# spine_0.net
KiCad netlist of a schematic drawn in Altium Designer
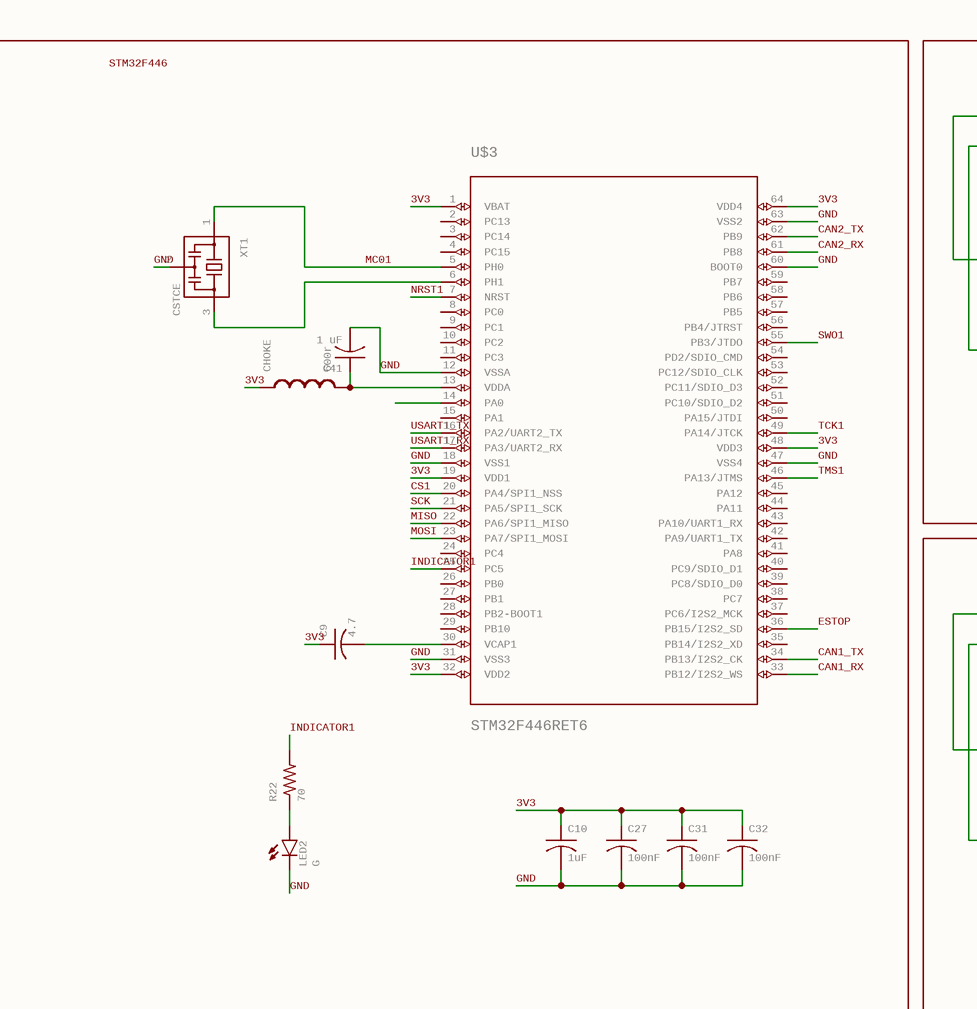
[diagram p0: spine_0.SchDoc, top left]
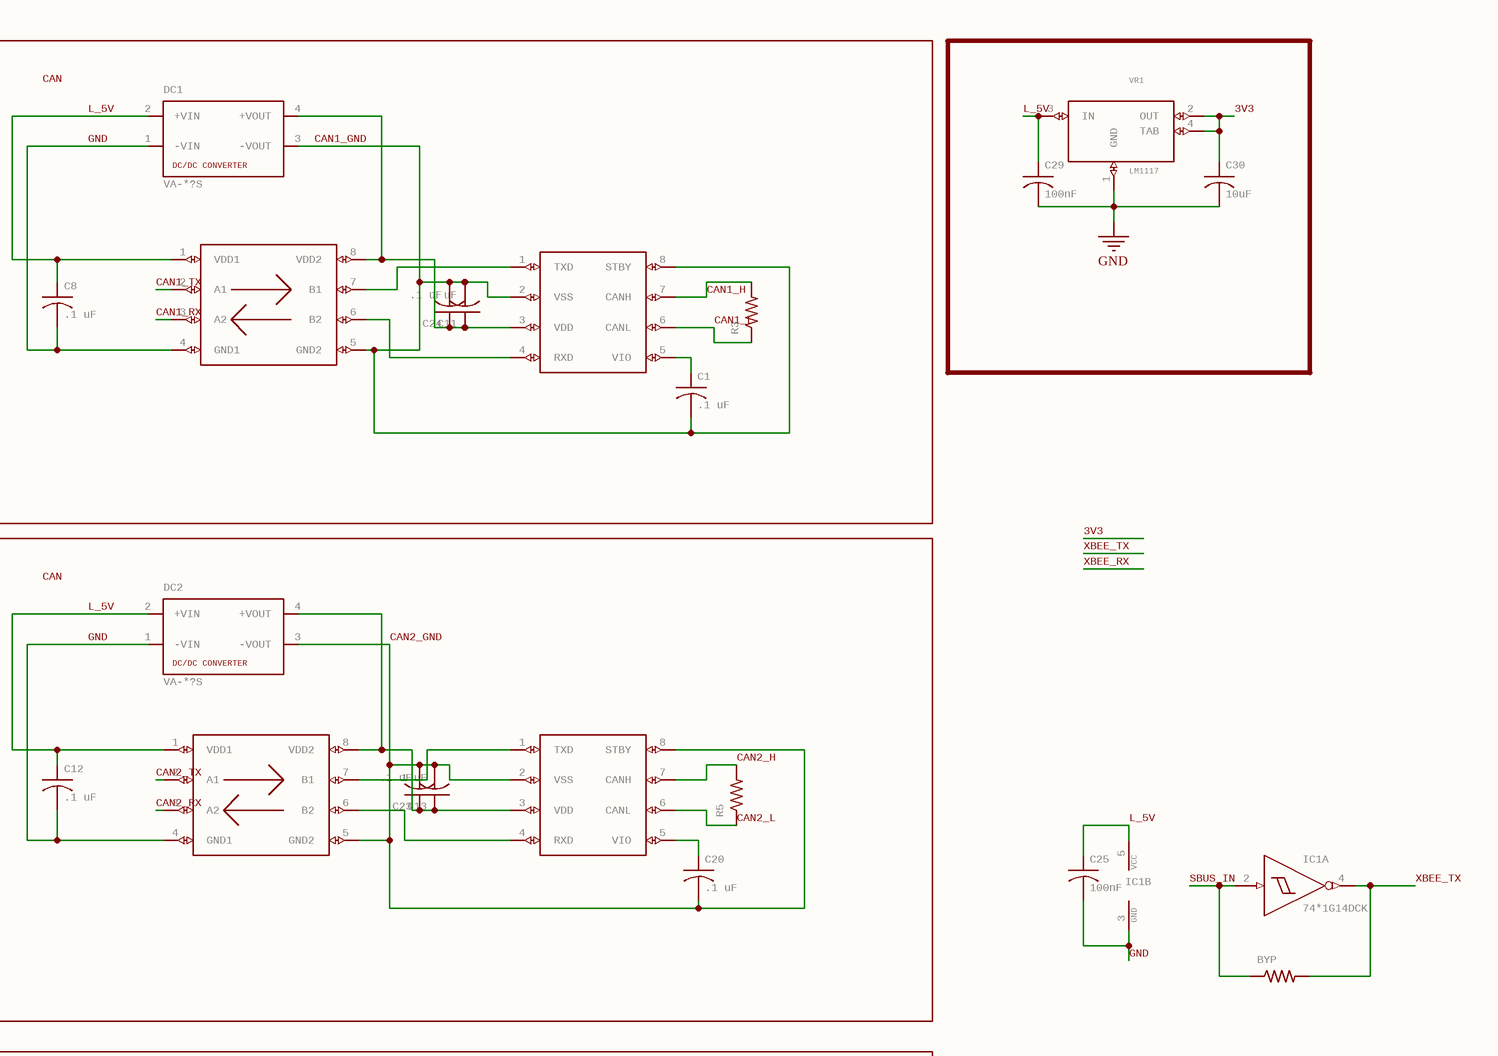
[diagram p1: spine_0.SchDoc, top right]
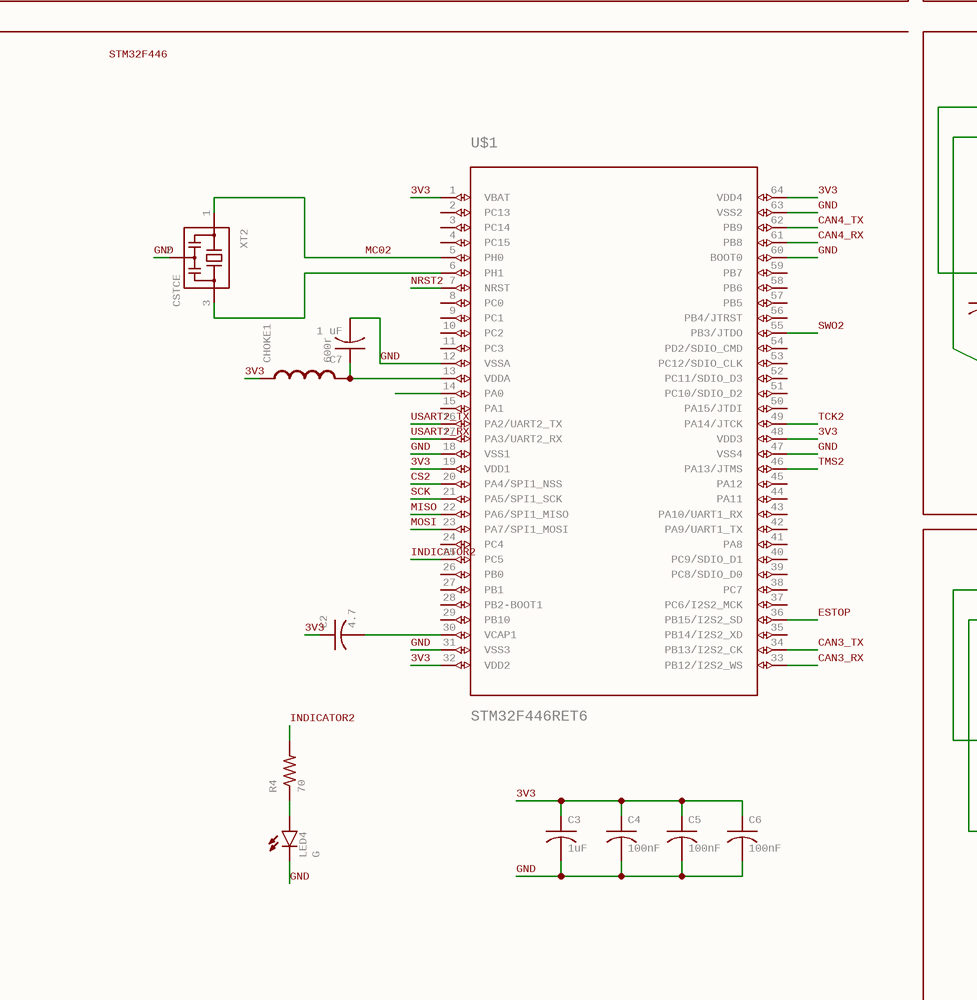
[diagram p2: spine_0.SchDoc, bottom left]
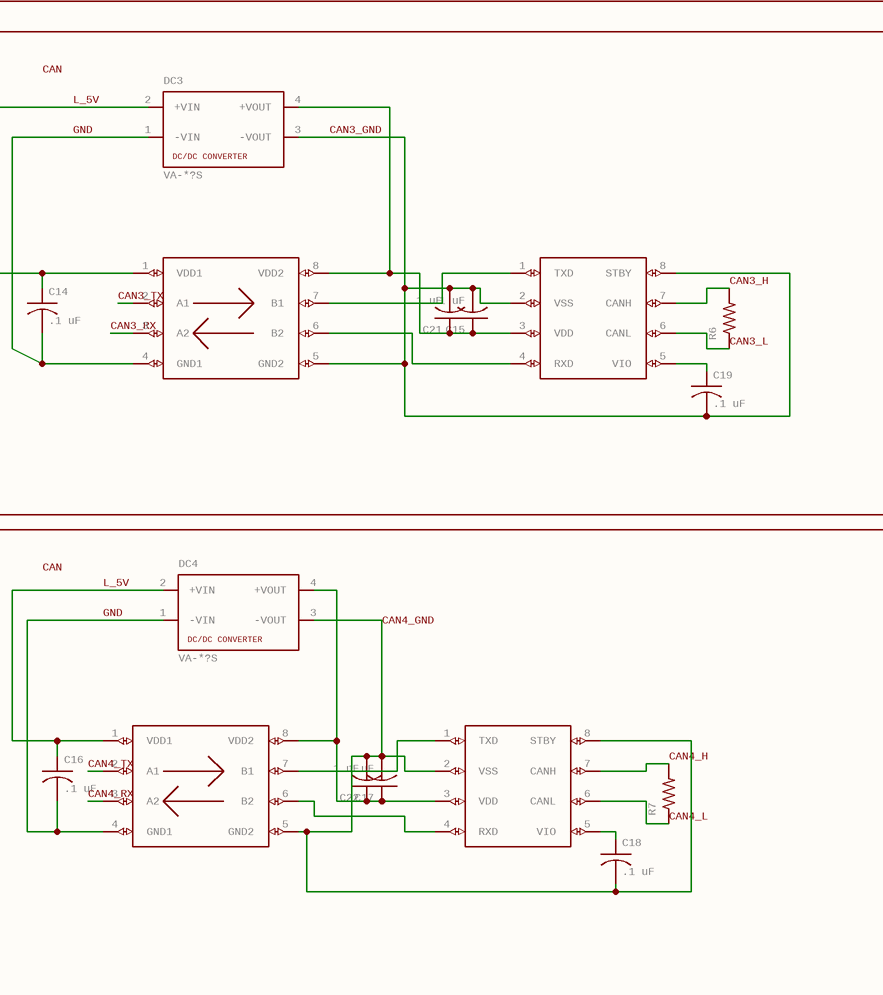
[diagram p3: spine_0.SchDoc, bottom right]

(export (version "E")
  (design (tool "Eeschema 10.0.6"))
  (components
    (comp (ref "BYP")
      (value "R-US_R0402")
      (footprint "R0402")
      (description "RESISTOR, American symbol")
      (libsource (lib "rcl") (part "R-US_R0402"))
    )
    (comp (ref "C1")
      (value ".1 uF")
      (footprint "C0603K")
      (description "CAPACITOR, American symbol")
      (libsource (lib "rcl") (part "C-USC0603K"))
    )
    (comp (ref "C2")
      (value "4.7")
      (footprint "C0603")
      (description "CAPACITOR, American symbol")
      (libsource (lib "rcl") (part "C-USC0603"))
    )
    (comp (ref "C3")
      (value "1uF")
      (footprint "C0603")
      (description "CAPACITOR, American symbol")
      (libsource (lib "rcl") (part "C-USC0603"))
    )
    (comp (ref "C4")
      (value "100nF")
      (footprint "C0603")
      (description "CAPACITOR, American symbol")
      (libsource (lib "rcl") (part "C-USC0603"))
    )
    (comp (ref "C5")
      (value "100nF")
      (footprint "C0603")
      (description "CAPACITOR, American symbol")
      (libsource (lib "rcl") (part "C-USC0603"))
    )
    (comp (ref "C6")
      (value "100nF")
      (footprint "C0603")
      (description "CAPACITOR, American symbol")
      (libsource (lib "rcl") (part "C-USC0603"))
    )
    (comp (ref "C7")
      (value "1 uF")
      (footprint "C0603")
      (description "CAPACITOR, American symbol")
      (libsource (lib "rcl") (part "C-USC0603"))
    )
    (comp (ref "C8")
      (value ".1 uF")
      (footprint "C0603K")
      (description "CAPACITOR, American symbol")
      (libsource (lib "rcl") (part "C-USC0603K"))
    )
    (comp (ref "C9")
      (value "4.7")
      (footprint "C0603")
      (description "CAPACITOR, American symbol")
      (libsource (lib "rcl") (part "C-USC0603"))
    )
    (comp (ref "C10")
      (value "1uF")
      (footprint "C0603")
      (description "CAPACITOR, American symbol")
      (libsource (lib "rcl") (part "C-USC0603"))
    )
    (comp (ref "C11")
      (value "1 uF")
      (footprint "C0603K")
      (description "CAPACITOR, American symbol")
      (libsource (lib "rcl") (part "C-USC0603K"))
    )
    (comp (ref "C12")
      (value ".1 uF")
      (footprint "C0603K")
      (description "CAPACITOR, American symbol")
      (libsource (lib "rcl") (part "C-USC0603K"))
    )
    (comp (ref "C13")
      (value "1 uF")
      (footprint "C0603K")
      (description "CAPACITOR, American symbol")
      (libsource (lib "rcl") (part "C-USC0603K"))
    )
    (comp (ref "C14")
      (value ".1 uF")
      (footprint "C0603K")
      (description "CAPACITOR, American symbol")
      (libsource (lib "rcl") (part "C-USC0603K"))
    )
    (comp (ref "C15")
      (value "1 uF")
      (footprint "C0603K")
      (description "CAPACITOR, American symbol")
      (libsource (lib "rcl") (part "C-USC0603K"))
    )
    (comp (ref "C16")
      (value ".1 uF")
      (footprint "C0603K")
      (description "CAPACITOR, American symbol")
      (libsource (lib "rcl") (part "C-USC0603K"))
    )
    (comp (ref "C17")
      (value "1 uF")
      (footprint "C0603K")
      (description "CAPACITOR, American symbol")
      (libsource (lib "rcl") (part "C-USC0603K"))
    )
    (comp (ref "C18")
      (value ".1 uF")
      (footprint "C0603K")
      (description "CAPACITOR, American symbol")
      (libsource (lib "rcl") (part "C-USC0603K"))
    )
    (comp (ref "C19")
      (value ".1 uF")
      (footprint "C0603K")
      (description "CAPACITOR, American symbol")
      (libsource (lib "rcl") (part "C-USC0603K"))
    )
    (comp (ref "C20")
      (value ".1 uF")
      (footprint "C0603K")
      (description "CAPACITOR, American symbol")
      (libsource (lib "rcl") (part "C-USC0603K"))
    )
    (comp (ref "C21")
      (value ".1 uF")
      (footprint "C0603K")
      (description "CAPACITOR, American symbol")
      (libsource (lib "rcl") (part "C-USC0603K"))
    )
    (comp (ref "C22")
      (value ".1 uF")
      (footprint "C0603K")
      (description "CAPACITOR, American symbol")
      (libsource (lib "rcl") (part "C-USC0603K"))
    )
    (comp (ref "C23")
      (value ".1 uF")
      (footprint "C0603K")
      (description "CAPACITOR, American symbol")
      (libsource (lib "rcl") (part "C-USC0603K"))
    )
    (comp (ref "C24")
      (value ".1 uF")
      (footprint "C0603K")
      (description "CAPACITOR, American symbol")
      (libsource (lib "rcl") (part "C-USC0603K"))
    )
    (comp (ref "C25")
      (value "100nF")
      (footprint "C0603")
      (description "CAPACITOR, American symbol")
      (libsource (lib "rcl") (part "C-USC0603"))
    )
    (comp (ref "C27")
      (value "100nF")
      (footprint "C0603")
      (description "CAPACITOR, American symbol")
      (libsource (lib "rcl") (part "C-USC0603"))
    )
    (comp (ref "C29")
      (value "100nF")
      (footprint "C0603")
      (description "CAPACITOR, American symbol")
      (libsource (lib "rcl") (part "C-USC0603"))
    )
    (comp (ref "C30")
      (value "10uF")
      (footprint "C0805K")
      (description "CAPACITOR, American symbol")
      (libsource (lib "rcl") (part "C-USC0805K"))
    )
    (comp (ref "C31")
      (value "100nF")
      (footprint "C0603")
      (description "CAPACITOR, American symbol")
      (libsource (lib "rcl") (part "C-USC0603"))
    )
    (comp (ref "C32")
      (value "100nF")
      (footprint "C0603")
      (description "CAPACITOR, American symbol")
      (libsource (lib "rcl") (part "C-USC0603"))
    )
    (comp (ref "C41")
      (value "1 uF")
      (footprint "C0603")
      (description "CAPACITOR, American symbol")
      (libsource (lib "rcl") (part "C-USC0603"))
    )
    (comp (ref "CHOKE")
      (value "600r")
      (footprint "0603")
      (libsource (lib "SparkFun-Passives") (part "INDUCTOR0603"))
    )
    (comp (ref "CHOKE1")
      (value "600r")
      (footprint "0603")
      (libsource (lib "SparkFun-Passives") (part "INDUCTOR0603"))
    )
    (comp (ref "DC1")
      (value "VA-*?S")
      (footprint "4SIL")
      (description "DC DC Converter Single Output, 1 Watt   Motien Technology Co.,Ltd. Source:  Data sheet")
      (fields
        (field (name "DC/DCCONVERTER") "DC/DC CONVERTER")
        (field (name "MF") "MF")
        (field (name "MPN") "MPN")
      )
      (libsource (lib "dc-dc-converter") (part "VA-*?S"))
    )
    (comp (ref "DC2")
      (value "VA-*?S")
      (footprint "4SIL")
      (description "DC DC Converter Single Output, 1 Watt   Motien Technology Co.,Ltd. Source:  Data sheet")
      (fields
        (field (name "DC/DCCONVERTER") "DC/DC CONVERTER")
        (field (name "MF") "MF")
        (field (name "MPN") "MPN")
      )
      (libsource (lib "dc-dc-converter") (part "VA-*?S"))
    )
    (comp (ref "DC3")
      (value "VA-*?S")
      (footprint "4SIL")
      (description "DC DC Converter Single Output, 1 Watt   Motien Technology Co.,Ltd. Source:  Data sheet")
      (fields
        (field (name "DC/DCCONVERTER") "DC/DC CONVERTER")
        (field (name "MF") "MF")
        (field (name "MPN") "MPN")
      )
      (libsource (lib "dc-dc-converter") (part "VA-*?S"))
    )
    (comp (ref "DC4")
      (value "VA-*?S")
      (footprint "4SIL")
      (description "DC DC Converter Single Output, 1 Watt   Motien Technology Co.,Ltd. Source:  Data sheet")
      (fields
        (field (name "DC/DCCONVERTER") "DC/DC CONVERTER")
        (field (name "MF") "MF")
        (field (name "MPN") "MPN")
      )
      (libsource (lib "dc-dc-converter") (part "VA-*?S"))
    )
    (comp (ref "IC1")
      (value "74*1G14DCK")
      (footprint "SC70-5")
      (description "Single Schmitt-Trigger Inverter Gate")
      (fields (field (name "GND") "GND") (field (name "VCC") "VCC"))
      (libsource (lib "74xx-little-us") (part "74*1G14DCK"))
    )
    (comp (ref "LED2") (value "G") (footprint "LED-0603") (libsource (lib "SparkFun-LED") (part "LED0603")))
    (comp (ref "LED4") (value "G") (footprint "LED-0603") (libsource (lib "SparkFun-LED") (part "LED0603")))
    (comp (ref "R3")
      (value "R-US_R0402")
      (footprint "R0402")
      (description "RESISTOR, American symbol")
      (libsource (lib "rcl") (part "R-US_R0402"))
    )
    (comp (ref "R4")
      (value "70")
      (footprint "R0603")
      (description "RESISTOR, American symbol")
      (libsource (lib "rcl") (part "R-US_R0603"))
    )
    (comp (ref "R5")
      (value "R-US_R0402")
      (footprint "R0402")
      (description "RESISTOR, American symbol")
      (libsource (lib "rcl") (part "R-US_R0402"))
    )
    (comp (ref "R6")
      (value "R-US_R0402")
      (footprint "R0402")
      (description "RESISTOR, American symbol")
      (libsource (lib "rcl") (part "R-US_R0402"))
    )
    (comp (ref "R7")
      (value "R-US_R0402")
      (footprint "R0402")
      (description "RESISTOR, American symbol")
      (libsource (lib "rcl") (part "R-US_R0402"))
    )
    (comp (ref "R22")
      (value "70")
      (footprint "R0603")
      (description "RESISTOR, American symbol")
      (libsource (lib "rcl") (part "R-US_R0603"))
    )
    (comp (ref "U$1")
      (value "STM32F446RET6")
      (footprint "TQFP64")
      (description "ARM DSP Chip used on the WAV Trigger board.")
      (fields (field (name "LIBRARYNAME") "BenLibrary"))
      (libsource (lib "BenLibrary") (part "STM32F446RET6"))
    )
    (comp (ref "U$3")
      (value "STM32F446RET6")
      (footprint "TQFP64")
      (description "ARM DSP Chip used on the WAV Trigger board.")
      (fields (field (name "LIBRARYNAME") "BenLibrary"))
      (libsource (lib "BenLibrary") (part "STM32F446RET6"))
    )
    (comp (ref "U$4")
      (value "MCP2561")
      (footprint "SO08")
      (fields (field (name "LIBRARYNAME") "BenLibrary"))
      (libsource (lib "BenLibrary") (part "MCP2561"))
    )
    (comp (ref "U$5")
      (value "MCP2561")
      (footprint "SO08")
      (fields (field (name "LIBRARYNAME") "BenLibrary"))
      (libsource (lib "BenLibrary") (part "MCP2561"))
    )
    (comp (ref "U$6")
      (value "MCP2561")
      (footprint "SO08")
      (fields (field (name "LIBRARYNAME") "BenLibrary"))
      (libsource (lib "BenLibrary") (part "MCP2561"))
    )
    (comp (ref "U$7")
      (value "MCP2561")
      (footprint "SO08")
      (fields (field (name "LIBRARYNAME") "BenLibrary"))
      (libsource (lib "BenLibrary") (part "MCP2561"))
    )
    (comp (ref "U$8")
      (value "SI8410")
      (footprint "SO08")
      (fields (field (name "LIBRARYNAME") "BenLibrary"))
      (libsource (lib "BenLibrary") (part "SI8410"))
    )
    (comp (ref "U$9")
      (value "SI8410")
      (footprint "SO08")
      (fields (field (name "LIBRARYNAME") "BenLibrary"))
      (libsource (lib "BenLibrary") (part "SI8410"))
    )
    (comp (ref "U$10")
      (value "SI8410")
      (footprint "SO08")
      (fields (field (name "LIBRARYNAME") "BenLibrary"))
      (libsource (lib "BenLibrary") (part "SI8410"))
    )
    (comp (ref "U$11")
      (value "SI8410")
      (footprint "SO08")
      (fields (field (name "LIBRARYNAME") "BenLibrary"))
      (libsource (lib "BenLibrary") (part "SI8410"))
    )
    (comp (ref "VR1")
      (value "LM1117")
      (footprint "SOT-223")
      (fields (field (name "LIBRARYNAME") "sc_usercreated"))
      (libsource (lib "sc_usercreated") (part "LM1117"))
    )
    (comp (ref "XT1")
      (value "CSTCE")
      (footprint "CSTCE")
      (fields (field (name "LIBRARYNAME") "sc_usercreated"))
      (libsource (lib "sc_usercreated") (part "CSTCE"))
    )
    (comp (ref "XT2")
      (value "CSTCE")
      (footprint "CSTCE")
      (fields (field (name "LIBRARYNAME") "sc_usercreated"))
      (libsource (lib "sc_usercreated") (part "CSTCE"))
    )
  )
  (nets
    (net (code "1") (name "/3V3") (class "Default")
      (node (ref "C10") (pin "1") (pinfunction "1_1") (pintype "passive"))
      (node (ref "C2") (pin "1") (pinfunction "1_1") (pintype "passive"))
      (node (ref "C27") (pin "1") (pinfunction "1_1") (pintype "passive"))
      (node (ref "C3") (pin "1") (pinfunction "1_1") (pintype "passive"))
      (node (ref "C30") (pin "1") (pinfunction "1_1") (pintype "passive"))
      (node (ref "C31") (pin "1") (pinfunction "1_1") (pintype "passive"))
      (node (ref "C32") (pin "1") (pinfunction "1_1") (pintype "passive"))
      (node (ref "C4") (pin "1") (pinfunction "1_1") (pintype "passive"))
      (node (ref "C5") (pin "1") (pinfunction "1_1") (pintype "passive"))
      (node (ref "C6") (pin "1") (pinfunction "1_1") (pintype "passive"))
      (node (ref "C9") (pin "1") (pinfunction "1_1") (pintype "passive"))
      (node (ref "CHOKE") (pin "1") (pinfunction "1_1") (pintype "passive"))
      (node (ref "CHOKE1") (pin "1") (pinfunction "1_1") (pintype "passive"))
      (node (ref "U$1") (pin "1") (pinfunction "VBAT_1") (pintype "bidirectional"))
      (node (ref "U$1") (pin "19") (pinfunction "VDD1_19") (pintype "bidirectional"))
      (node (ref "U$1") (pin "32") (pinfunction "VDD2_32") (pintype "bidirectional"))
      (node (ref "U$1") (pin "48") (pinfunction "VDD3_48") (pintype "bidirectional"))
      (node (ref "U$1") (pin "64") (pinfunction "VDD4_64") (pintype "bidirectional"))
      (node (ref "U$3") (pin "1") (pinfunction "VBAT_1") (pintype "bidirectional"))
      (node (ref "U$3") (pin "19") (pinfunction "VDD1_19") (pintype "bidirectional"))
      (node (ref "U$3") (pin "32") (pinfunction "VDD2_32") (pintype "bidirectional"))
      (node (ref "U$3") (pin "48") (pinfunction "VDD3_48") (pintype "bidirectional"))
      (node (ref "U$3") (pin "64") (pinfunction "VDD4_64") (pintype "bidirectional"))
      (node (ref "VR1") (pin "2") (pinfunction "OUT_2") (pintype "bidirectional"))
      (node (ref "VR1") (pin "4") (pinfunction "TAB_4") (pintype "bidirectional"))
    )
    (net (code "2") (name "/CAN1_GND") (class "Default")
      (node (ref "C1") (pin "2") (pinfunction "2_2") (pintype "passive"))
      (node (ref "C11") (pin "2") (pinfunction "2_2") (pintype "passive"))
      (node (ref "C24") (pin "2") (pinfunction "2_2") (pintype "passive"))
      (node (ref "DC1") (pin "3") (pinfunction "-VOUT_3") (pintype "passive"))
      (node (ref "U$4") (pin "2") (pinfunction "VSS_2") (pintype "bidirectional"))
      (node (ref "U$4") (pin "8") (pinfunction "STBY_8") (pintype "bidirectional"))
      (node (ref "U$8") (pin "5") (pinfunction "GND2_5") (pintype "bidirectional"))
    )
    (net (code "3") (name "/CAN1_H") (class "Default")
      (node (ref "R3") (pin "2") (pinfunction "2_2") (pintype "passive"))
      (node (ref "U$4") (pin "7") (pinfunction "CANH_7") (pintype "bidirectional"))
    )
    (net (code "4") (name "/CAN1_L") (class "Default")
      (node (ref "R3") (pin "1") (pinfunction "1_1") (pintype "passive"))
      (node (ref "U$4") (pin "6") (pinfunction "CANL_6") (pintype "bidirectional"))
    )
    (net (code "5") (name "/CAN1_RX") (class "Default")
      (node (ref "U$3") (pin "33") (pinfunction "PB12/I2S2_WS_33") (pintype "bidirectional"))
      (node (ref "U$8") (pin "3") (pinfunction "A2_3") (pintype "bidirectional"))
    )
    (net (code "6") (name "/CAN1_TX") (class "Default")
      (node (ref "U$3") (pin "34") (pinfunction "PB13/I2S2_CK_34") (pintype "bidirectional"))
      (node (ref "U$8") (pin "2") (pinfunction "A1_2") (pintype "bidirectional"))
    )
    (net (code "7") (name "/CAN2_GND") (class "Default")
      (node (ref "C13") (pin "2") (pinfunction "2_2") (pintype "passive"))
      (node (ref "C20") (pin "2") (pinfunction "2_2") (pintype "passive"))
      (node (ref "C23") (pin "2") (pinfunction "2_2") (pintype "passive"))
      (node (ref "DC2") (pin "3") (pinfunction "-VOUT_3") (pintype "passive"))
      (node (ref "U$10") (pin "5") (pinfunction "GND2_5") (pintype "bidirectional"))
      (node (ref "U$5") (pin "2") (pinfunction "VSS_2") (pintype "bidirectional"))
      (node (ref "U$5") (pin "8") (pinfunction "STBY_8") (pintype "bidirectional"))
    )
    (net (code "8") (name "/CAN2_H") (class "Default")
      (node (ref "R5") (pin "2") (pinfunction "2_2") (pintype "passive"))
      (node (ref "U$5") (pin "7") (pinfunction "CANH_7") (pintype "bidirectional"))
    )
    (net (code "9") (name "/CAN2_L") (class "Default")
      (node (ref "R5") (pin "1") (pinfunction "1_1") (pintype "passive"))
      (node (ref "U$5") (pin "6") (pinfunction "CANL_6") (pintype "bidirectional"))
    )
    (net (code "10") (name "/CAN2_RX") (class "Default")
      (node (ref "U$10") (pin "3") (pinfunction "A2_3") (pintype "bidirectional"))
      (node (ref "U$3") (pin "61") (pinfunction "PB8_61") (pintype "bidirectional"))
    )
    (net (code "11") (name "/CAN2_TX") (class "Default")
      (node (ref "U$10") (pin "2") (pinfunction "A1_2") (pintype "bidirectional"))
      (node (ref "U$3") (pin "62") (pinfunction "PB9_62") (pintype "bidirectional"))
    )
    (net (code "12") (name "/CAN3_GND") (class "Default")
      (node (ref "C15") (pin "2") (pinfunction "2_2") (pintype "passive"))
      (node (ref "C19") (pin "2") (pinfunction "2_2") (pintype "passive"))
      (node (ref "C21") (pin "2") (pinfunction "2_2") (pintype "passive"))
      (node (ref "DC3") (pin "3") (pinfunction "-VOUT_3") (pintype "passive"))
      (node (ref "U$6") (pin "2") (pinfunction "VSS_2") (pintype "bidirectional"))
      (node (ref "U$6") (pin "8") (pinfunction "STBY_8") (pintype "bidirectional"))
      (node (ref "U$9") (pin "5") (pinfunction "GND2_5") (pintype "bidirectional"))
    )
    (net (code "13") (name "/CAN3_H") (class "Default")
      (node (ref "R6") (pin "2") (pinfunction "2_2") (pintype "passive"))
      (node (ref "U$6") (pin "7") (pinfunction "CANH_7") (pintype "bidirectional"))
    )
    (net (code "14") (name "/CAN3_L") (class "Default")
      (node (ref "R6") (pin "1") (pinfunction "1_1") (pintype "passive"))
      (node (ref "U$6") (pin "6") (pinfunction "CANL_6") (pintype "bidirectional"))
    )
    (net (code "15") (name "/CAN3_RX") (class "Default")
      (node (ref "U$1") (pin "33") (pinfunction "PB12/I2S2_WS_33") (pintype "bidirectional"))
      (node (ref "U$9") (pin "3") (pinfunction "A2_3") (pintype "bidirectional"))
    )
    (net (code "16") (name "/CAN3_TX") (class "Default")
      (node (ref "U$1") (pin "34") (pinfunction "PB13/I2S2_CK_34") (pintype "bidirectional"))
      (node (ref "U$9") (pin "2") (pinfunction "A1_2") (pintype "bidirectional"))
    )
    (net (code "17") (name "/CAN4_GND") (class "Default")
      (node (ref "C17") (pin "2") (pinfunction "2_2") (pintype "passive"))
      (node (ref "C18") (pin "2") (pinfunction "2_2") (pintype "passive"))
      (node (ref "C22") (pin "2") (pinfunction "2_2") (pintype "passive"))
      (node (ref "DC4") (pin "3") (pinfunction "-VOUT_3") (pintype "passive"))
      (node (ref "U$11") (pin "5") (pinfunction "GND2_5") (pintype "bidirectional"))
      (node (ref "U$7") (pin "2") (pinfunction "VSS_2") (pintype "bidirectional"))
      (node (ref "U$7") (pin "8") (pinfunction "STBY_8") (pintype "bidirectional"))
    )
    (net (code "18") (name "/CAN4_H") (class "Default")
      (node (ref "R7") (pin "2") (pinfunction "2_2") (pintype "passive"))
      (node (ref "U$7") (pin "7") (pinfunction "CANH_7") (pintype "bidirectional"))
    )
    (net (code "19") (name "/CAN4_L") (class "Default")
      (node (ref "R7") (pin "1") (pinfunction "1_1") (pintype "passive"))
      (node (ref "U$7") (pin "6") (pinfunction "CANL_6") (pintype "bidirectional"))
    )
    (net (code "20") (name "/CAN4_RX") (class "Default")
      (node (ref "U$1") (pin "61") (pinfunction "PB8_61") (pintype "bidirectional"))
      (node (ref "U$11") (pin "3") (pinfunction "A2_3") (pintype "bidirectional"))
    )
    (net (code "21") (name "/CAN4_TX") (class "Default")
      (node (ref "U$1") (pin "62") (pinfunction "PB9_62") (pintype "bidirectional"))
      (node (ref "U$11") (pin "2") (pinfunction "A1_2") (pintype "bidirectional"))
    )
    (net (code "22") (name "/CS1") (class "Default")
      (node (ref "U$3") (pin "20") (pinfunction "PA4/SPI1_NSS_20") (pintype "bidirectional"))
    )
    (net (code "23") (name "/CS2") (class "Default")
      (node (ref "U$1") (pin "20") (pinfunction "PA4/SPI1_NSS_20") (pintype "bidirectional"))
    )
    (net (code "24") (name "/ESTOP") (class "Default")
      (node (ref "U$1") (pin "36") (pinfunction "PB15/I2S2_SD_36") (pintype "bidirectional"))
      (node (ref "U$3") (pin "36") (pinfunction "PB15/I2S2_SD_36") (pintype "bidirectional"))
    )
    (net (code "25") (name "/INDICATOR1") (class "Default")
      (node (ref "R22") (pin "2") (pinfunction "2_2") (pintype "passive"))
      (node (ref "U$3") (pin "25") (pinfunction "PC5_25") (pintype "bidirectional"))
    )
    (net (code "26") (name "/INDICATOR2") (class "Default")
      (node (ref "R4") (pin "2") (pinfunction "2_2") (pintype "passive"))
      (node (ref "U$1") (pin "25") (pinfunction "PC5_25") (pintype "bidirectional"))
    )
    (net (code "27") (name "/L_5V") (class "Default")
      (node (ref "C12") (pin "1") (pinfunction "1_1") (pintype "passive"))
      (node (ref "C14") (pin "1") (pinfunction "1_1") (pintype "passive"))
      (node (ref "C16") (pin "1") (pinfunction "1_1") (pintype "passive"))
      (node (ref "C25") (pin "1") (pinfunction "1_1") (pintype "passive"))
      (node (ref "C29") (pin "1") (pinfunction "1_1") (pintype "passive"))
      (node (ref "C8") (pin "1") (pinfunction "1_1") (pintype "passive"))
      (node (ref "DC1") (pin "2") (pinfunction "+VIN_2") (pintype "passive"))
      (node (ref "DC2") (pin "2") (pinfunction "+VIN_2") (pintype "passive"))
      (node (ref "DC3") (pin "2") (pinfunction "+VIN_2") (pintype "passive"))
      (node (ref "DC4") (pin "2") (pinfunction "+VIN_2") (pintype "passive"))
      (node (ref "IC1") (pin "5") (pinfunction "VCC_5") (pintype "power_in"))
      (node (ref "U$10") (pin "1") (pinfunction "VDD1_1") (pintype "bidirectional"))
      (node (ref "U$11") (pin "1") (pinfunction "VDD1_1") (pintype "bidirectional"))
      (node (ref "U$8") (pin "1") (pinfunction "VDD1_1") (pintype "bidirectional"))
      (node (ref "U$9") (pin "1") (pinfunction "VDD1_1") (pintype "bidirectional"))
      (node (ref "VR1") (pin "3") (pinfunction "IN_3") (pintype "bidirectional"))
    )
    (net (code "28") (name "/MC01") (class "Default")
      (node (ref "U$3") (pin "5") (pinfunction "PH0_5") (pintype "bidirectional"))
      (node (ref "XT1") (pin "1") (pinfunction "1_1") (pintype "passive"))
    )
    (net (code "29") (name "/MC02") (class "Default")
      (node (ref "U$1") (pin "5") (pinfunction "PH0_5") (pintype "bidirectional"))
      (node (ref "XT2") (pin "1") (pinfunction "1_1") (pintype "passive"))
    )
    (net (code "30") (name "/MISO") (class "Default")
      (node (ref "U$1") (pin "22") (pinfunction "PA6/SPI1_MISO_22") (pintype "bidirectional"))
      (node (ref "U$3") (pin "22") (pinfunction "PA6/SPI1_MISO_22") (pintype "bidirectional"))
    )
    (net (code "31") (name "/MOSI") (class "Default")
      (node (ref "U$1") (pin "23") (pinfunction "PA7/SPI1_MOSI_23") (pintype "bidirectional"))
      (node (ref "U$3") (pin "23") (pinfunction "PA7/SPI1_MOSI_23") (pintype "bidirectional"))
    )
    (net (code "32") (name "/NRST1") (class "Default")
      (node (ref "U$3") (pin "7") (pinfunction "NRST_7") (pintype "bidirectional"))
    )
    (net (code "33") (name "/NRST2") (class "Default")
      (node (ref "U$1") (pin "7") (pinfunction "NRST_7") (pintype "bidirectional"))
    )
    (net (code "34") (name "/SBUS_IN") (class "Default")
      (node (ref "BYP") (pin "1") (pinfunction "1_1") (pintype "passive"))
      (node (ref "IC1") (pin "2") (pinfunction "I_2") (pintype "input"))
    )
    (net (code "35") (name "/SCK") (class "Default")
      (node (ref "U$1") (pin "21") (pinfunction "PA5/SPI1_SCK_21") (pintype "bidirectional"))
      (node (ref "U$3") (pin "21") (pinfunction "PA5/SPI1_SCK_21") (pintype "bidirectional"))
    )
    (net (code "36") (name "/SWO1") (class "Default")
      (node (ref "U$3") (pin "55") (pinfunction "PB3/JTDO_55") (pintype "bidirectional"))
    )
    (net (code "37") (name "/SWO2") (class "Default")
      (node (ref "U$1") (pin "55") (pinfunction "PB3/JTDO_55") (pintype "bidirectional"))
    )
    (net (code "38") (name "/TCK1") (class "Default")
      (node (ref "U$3") (pin "49") (pinfunction "PA14/JTCK_49") (pintype "bidirectional"))
    )
    (net (code "39") (name "/TCK2") (class "Default")
      (node (ref "U$1") (pin "49") (pinfunction "PA14/JTCK_49") (pintype "bidirectional"))
    )
    (net (code "40") (name "/TMS1") (class "Default")
      (node (ref "U$3") (pin "46") (pinfunction "PA13/JTMS_46") (pintype "bidirectional"))
    )
    (net (code "41") (name "/TMS2") (class "Default")
      (node (ref "U$1") (pin "46") (pinfunction "PA13/JTMS_46") (pintype "bidirectional"))
    )
    (net (code "42") (name "/USART1_RX") (class "Default")
      (node (ref "U$3") (pin "17") (pinfunction "PA3/UART2_RX_17") (pintype "bidirectional"))
    )
    (net (code "43") (name "/USART1_TX") (class "Default")
      (node (ref "U$3") (pin "16") (pinfunction "PA2/UART2_TX_16") (pintype "bidirectional"))
    )
    (net (code "44") (name "/USART2_RX") (class "Default")
      (node (ref "U$1") (pin "17") (pinfunction "PA3/UART2_RX_17") (pintype "bidirectional"))
    )
    (net (code "45") (name "/USART2_TX") (class "Default")
      (node (ref "U$1") (pin "16") (pinfunction "PA2/UART2_TX_16") (pintype "bidirectional"))
    )
    (net (code "47") (name "/XBEE_TX") (class "Default")
      (node (ref "BYP") (pin "2") (pinfunction "2_2") (pintype "passive"))
      (node (ref "IC1") (pin "4") (pinfunction "O_4") (pintype "output"))
    )
    (net (code "48") (name "GND") (class "Default")
      (node (ref "C10") (pin "2") (pinfunction "2_2") (pintype "passive"))
      (node (ref "C12") (pin "2") (pinfunction "2_2") (pintype "passive"))
      (node (ref "C14") (pin "2") (pinfunction "2_2") (pintype "passive"))
      (node (ref "C16") (pin "2") (pinfunction "2_2") (pintype "passive"))
      (node (ref "C25") (pin "2") (pinfunction "2_2") (pintype "passive"))
      (node (ref "C27") (pin "2") (pinfunction "2_2") (pintype "passive"))
      (node (ref "C29") (pin "2") (pinfunction "2_2") (pintype "passive"))
      (node (ref "C3") (pin "2") (pinfunction "2_2") (pintype "passive"))
      (node (ref "C30") (pin "2") (pinfunction "2_2") (pintype "passive"))
      (node (ref "C31") (pin "2") (pinfunction "2_2") (pintype "passive"))
      (node (ref "C32") (pin "2") (pinfunction "2_2") (pintype "passive"))
      (node (ref "C4") (pin "2") (pinfunction "2_2") (pintype "passive"))
      (node (ref "C41") (pin "2") (pinfunction "2_2") (pintype "passive"))
      (node (ref "C5") (pin "2") (pinfunction "2_2") (pintype "passive"))
      (node (ref "C6") (pin "2") (pinfunction "2_2") (pintype "passive"))
      (node (ref "C7") (pin "2") (pinfunction "2_2") (pintype "passive"))
      (node (ref "C8") (pin "2") (pinfunction "2_2") (pintype "passive"))
      (node (ref "DC1") (pin "1") (pinfunction "-VIN_1") (pintype "passive"))
      (node (ref "DC2") (pin "1") (pinfunction "-VIN_1") (pintype "passive"))
      (node (ref "DC3") (pin "1") (pinfunction "-VIN_1") (pintype "passive"))
      (node (ref "DC4") (pin "1") (pinfunction "-VIN_1") (pintype "passive"))
      (node (ref "IC1") (pin "3") (pinfunction "GND_3") (pintype "power_in"))
      (node (ref "LED2") (pin "C") (pinfunction "C_C") (pintype "passive"))
      (node (ref "LED4") (pin "C") (pinfunction "C_C") (pintype "passive"))
      (node (ref "U$1") (pin "12") (pinfunction "VSSA_12") (pintype "bidirectional"))
      (node (ref "U$1") (pin "18") (pinfunction "VSS1_18") (pintype "bidirectional"))
      (node (ref "U$1") (pin "31") (pinfunction "VSS3_31") (pintype "bidirectional"))
      (node (ref "U$1") (pin "47") (pinfunction "VSS4_47") (pintype "bidirectional"))
      (node (ref "U$1") (pin "60") (pinfunction "BOOT0_60") (pintype "bidirectional"))
      (node (ref "U$1") (pin "63") (pinfunction "VSS2_63") (pintype "bidirectional"))
      (node (ref "U$10") (pin "4") (pinfunction "GND1_4") (pintype "bidirectional"))
      (node (ref "U$11") (pin "4") (pinfunction "GND1_4") (pintype "bidirectional"))
      (node (ref "U$3") (pin "12") (pinfunction "VSSA_12") (pintype "bidirectional"))
      (node (ref "U$3") (pin "18") (pinfunction "VSS1_18") (pintype "bidirectional"))
      (node (ref "U$3") (pin "31") (pinfunction "VSS3_31") (pintype "bidirectional"))
      (node (ref "U$3") (pin "47") (pinfunction "VSS4_47") (pintype "bidirectional"))
      (node (ref "U$3") (pin "60") (pinfunction "BOOT0_60") (pintype "bidirectional"))
      (node (ref "U$3") (pin "63") (pinfunction "VSS2_63") (pintype "bidirectional"))
      (node (ref "U$8") (pin "4") (pinfunction "GND1_4") (pintype "bidirectional"))
      (node (ref "U$9") (pin "4") (pinfunction "GND1_4") (pintype "bidirectional"))
      (node (ref "VR1") (pin "1") (pinfunction "GND_1") (pintype "bidirectional"))
      (node (ref "XT1") (pin "2") (pinfunction "2_2") (pintype "passive"))
      (node (ref "XT2") (pin "2") (pinfunction "2_2") (pintype "passive"))
    )
    (net (code "49") (name "Net-(DC1-+VOUT)") (class "Default")
      (node (ref "C11") (pin "1") (pinfunction "1_1") (pintype "passive"))
      (node (ref "C24") (pin "1") (pinfunction "1_1") (pintype "passive"))
      (node (ref "DC1") (pin "4") (pinfunction "+VOUT_4") (pintype "passive"))
      (node (ref "U$4") (pin "3") (pinfunction "VDD_3") (pintype "bidirectional"))
      (node (ref "U$8") (pin "8") (pinfunction "VDD2_8") (pintype "bidirectional"))
    )
    (net (code "50") (name "Net-(DC2-+VOUT)") (class "Default")
      (node (ref "C13") (pin "1") (pinfunction "1_1") (pintype "passive"))
      (node (ref "C23") (pin "1") (pinfunction "1_1") (pintype "passive"))
      (node (ref "DC2") (pin "4") (pinfunction "+VOUT_4") (pintype "passive"))
      (node (ref "U$10") (pin "8") (pinfunction "VDD2_8") (pintype "bidirectional"))
      (node (ref "U$5") (pin "3") (pinfunction "VDD_3") (pintype "bidirectional"))
    )
    (net (code "51") (name "Net-(DC3-+VOUT)") (class "Default")
      (node (ref "C15") (pin "1") (pinfunction "1_1") (pintype "passive"))
      (node (ref "C21") (pin "1") (pinfunction "1_1") (pintype "passive"))
      (node (ref "DC3") (pin "4") (pinfunction "+VOUT_4") (pintype "passive"))
      (node (ref "U$6") (pin "3") (pinfunction "VDD_3") (pintype "bidirectional"))
      (node (ref "U$9") (pin "8") (pinfunction "VDD2_8") (pintype "bidirectional"))
    )
    (net (code "52") (name "Net-(DC4-+VOUT)") (class "Default")
      (node (ref "C17") (pin "1") (pinfunction "1_1") (pintype "passive"))
      (node (ref "C22") (pin "1") (pinfunction "1_1") (pintype "passive"))
      (node (ref "DC4") (pin "4") (pinfunction "+VOUT_4") (pintype "passive"))
      (node (ref "U$11") (pin "8") (pinfunction "VDD2_8") (pintype "bidirectional"))
      (node (ref "U$7") (pin "3") (pinfunction "VDD_3") (pintype "bidirectional"))
    )
    (net (code "53") (name "Net-(LED2-PadA)") (class "Default")
      (node (ref "LED2") (pin "A") (pinfunction "A_A") (pintype "passive"))
      (node (ref "R22") (pin "1") (pinfunction "1_1") (pintype "passive"))
    )
    (net (code "54") (name "Net-(LED4-PadA)") (class "Default")
      (node (ref "LED4") (pin "A") (pinfunction "A_A") (pintype "passive"))
      (node (ref "R4") (pin "1") (pinfunction "1_1") (pintype "passive"))
    )
    (net (code "55") (name "Net-(U$1-PH1)") (class "Default")
      (node (ref "U$1") (pin "6") (pinfunction "PH1_6") (pintype "bidirectional"))
      (node (ref "XT2") (pin "3") (pinfunction "3_3") (pintype "passive"))
    )
    (net (code "56") (name "Net-(U$1-VCAP1)") (class "Default")
      (node (ref "C2") (pin "2") (pinfunction "2_2") (pintype "passive"))
      (node (ref "U$1") (pin "30") (pinfunction "VCAP1_30") (pintype "bidirectional"))
    )
    (net (code "57") (name "Net-(U$1-VDDA)") (class "Default")
      (node (ref "C7") (pin "1") (pinfunction "1_1") (pintype "passive"))
      (node (ref "CHOKE1") (pin "2") (pinfunction "2_2") (pintype "passive"))
      (node (ref "U$1") (pin "13") (pinfunction "VDDA_13") (pintype "bidirectional"))
    )
    (net (code "58") (name "Net-(U$3-PH1)") (class "Default")
      (node (ref "U$3") (pin "6") (pinfunction "PH1_6") (pintype "bidirectional"))
      (node (ref "XT1") (pin "3") (pinfunction "3_3") (pintype "passive"))
    )
    (net (code "59") (name "Net-(U$3-VCAP1)") (class "Default")
      (node (ref "C9") (pin "2") (pinfunction "2_2") (pintype "passive"))
      (node (ref "U$3") (pin "30") (pinfunction "VCAP1_30") (pintype "bidirectional"))
    )
    (net (code "60") (name "Net-(U$3-VDDA)") (class "Default")
      (node (ref "C41") (pin "1") (pinfunction "1_1") (pintype "passive"))
      (node (ref "CHOKE") (pin "2") (pinfunction "2_2") (pintype "passive"))
      (node (ref "U$3") (pin "13") (pinfunction "VDDA_13") (pintype "bidirectional"))
    )
    (net (code "61") (name "Net-(U$4-RXD)") (class "Default")
      (node (ref "U$4") (pin "4") (pinfunction "RXD_4") (pintype "bidirectional"))
      (node (ref "U$8") (pin "6") (pinfunction "B2_6") (pintype "bidirectional"))
    )
    (net (code "62") (name "Net-(U$4-TXD)") (class "Default")
      (node (ref "U$4") (pin "1") (pinfunction "TXD_1") (pintype "bidirectional"))
      (node (ref "U$8") (pin "7") (pinfunction "B1_7") (pintype "bidirectional"))
    )
    (net (code "63") (name "Net-(U$4-VIO)") (class "Default")
      (node (ref "C1") (pin "1") (pinfunction "1_1") (pintype "passive"))
      (node (ref "U$4") (pin "5") (pinfunction "VIO_5") (pintype "bidirectional"))
    )
    (net (code "64") (name "Net-(U$5-VIO)") (class "Default")
      (node (ref "C20") (pin "1") (pinfunction "1_1") (pintype "passive"))
      (node (ref "U$5") (pin "5") (pinfunction "VIO_5") (pintype "bidirectional"))
    )
    (net (code "65") (name "Net-(U$6-RXD)") (class "Default")
      (node (ref "U$6") (pin "4") (pinfunction "RXD_4") (pintype "bidirectional"))
      (node (ref "U$9") (pin "6") (pinfunction "B2_6") (pintype "bidirectional"))
    )
    (net (code "66") (name "Net-(U$6-TXD)") (class "Default")
      (node (ref "U$6") (pin "1") (pinfunction "TXD_1") (pintype "bidirectional"))
      (node (ref "U$9") (pin "7") (pinfunction "B1_7") (pintype "bidirectional"))
    )
    (net (code "67") (name "Net-(U$6-VIO)") (class "Default")
      (node (ref "C19") (pin "1") (pinfunction "1_1") (pintype "passive"))
      (node (ref "U$6") (pin "5") (pinfunction "VIO_5") (pintype "bidirectional"))
    )
    (net (code "68") (name "Net-(U$7-VIO)") (class "Default")
      (node (ref "C18") (pin "1") (pinfunction "1_1") (pintype "passive"))
      (node (ref "U$7") (pin "5") (pinfunction "VIO_5") (pintype "bidirectional"))
    )
    (net (code "69") (name "Net-(U$10-B1)") (class "Default")
      (node (ref "U$10") (pin "7") (pinfunction "B1_7") (pintype "bidirectional"))
      (node (ref "U$5") (pin "1") (pinfunction "TXD_1") (pintype "bidirectional"))
    )
    (net (code "70") (name "Net-(U$10-B2)") (class "Default")
      (node (ref "U$10") (pin "6") (pinfunction "B2_6") (pintype "bidirectional"))
      (node (ref "U$5") (pin "4") (pinfunction "RXD_4") (pintype "bidirectional"))
    )
    (net (code "71") (name "Net-(U$11-B1)") (class "Default")
      (node (ref "U$11") (pin "7") (pinfunction "B1_7") (pintype "bidirectional"))
      (node (ref "U$7") (pin "1") (pinfunction "TXD_1") (pintype "bidirectional"))
    )
    (net (code "72") (name "Net-(U$11-B2)") (class "Default")
      (node (ref "U$11") (pin "6") (pinfunction "B2_6") (pintype "bidirectional"))
      (node (ref "U$7") (pin "4") (pinfunction "RXD_4") (pintype "bidirectional"))
    )
    (net (code "73") (name "unconnected-(U$1-PA0-Pad14)") (class "Default")
      (node (ref "U$1") (pin "14") (pinfunction "PA0_14") (pintype "bidirectional"))
    )
    (net (code "74") (name "unconnected-(U$1-PA1-Pad15)") (class "Default")
      (node (ref "U$1") (pin "15") (pinfunction "PA1_15") (pintype "bidirectional"))
    )
    (net (code "75") (name "unconnected-(U$1-PA8-Pad41)") (class "Default")
      (node (ref "U$1") (pin "41") (pinfunction "PA8_41") (pintype "bidirectional"))
    )
    (net (code "76") (name "unconnected-(U$1-PA9{slash}UART1_TX-Pad42)") (class "Default")
      (node (ref "U$1") (pin "42") (pinfunction "PA9/UART1_TX_42") (pintype "bidirectional"))
    )
    (net (code "77") (name "unconnected-(U$1-PA10{slash}UART1_RX-Pad43)") (class "Default")
      (node (ref "U$1") (pin "43") (pinfunction "PA10/UART1_RX_43") (pintype "bidirectional"))
    )
    (net (code "78") (name "unconnected-(U$1-PA11-Pad44)") (class "Default")
      (node (ref "U$1") (pin "44") (pinfunction "PA11_44") (pintype "bidirectional"))
    )
    (net (code "79") (name "unconnected-(U$1-PA12-Pad45)") (class "Default")
      (node (ref "U$1") (pin "45") (pinfunction "PA12_45") (pintype "bidirectional"))
    )
    (net (code "80") (name "unconnected-(U$1-PA15{slash}JTDI-Pad50)") (class "Default")
      (node (ref "U$1") (pin "50") (pinfunction "PA15/JTDI_50") (pintype "bidirectional"))
    )
    (net (code "81") (name "unconnected-(U$1-PB0-Pad26)") (class "Default")
      (node (ref "U$1") (pin "26") (pinfunction "PB0_26") (pintype "bidirectional"))
    )
    (net (code "82") (name "unconnected-(U$1-PB1-Pad27)") (class "Default")
      (node (ref "U$1") (pin "27") (pinfunction "PB1_27") (pintype "bidirectional"))
    )
    (net (code "83") (name "unconnected-(U$1-PB2-BOOT1-Pad28)") (class "Default")
      (node (ref "U$1") (pin "28") (pinfunction "PB2-BOOT1_28") (pintype "bidirectional"))
    )
    (net (code "84") (name "unconnected-(U$1-PB4{slash}JTRST-Pad56)") (class "Default")
      (node (ref "U$1") (pin "56") (pinfunction "PB4/JTRST_56") (pintype "bidirectional"))
    )
    (net (code "85") (name "unconnected-(U$1-PB5-Pad57)") (class "Default")
      (node (ref "U$1") (pin "57") (pinfunction "PB5_57") (pintype "bidirectional"))
    )
    (net (code "86") (name "unconnected-(U$1-PB6-Pad58)") (class "Default")
      (node (ref "U$1") (pin "58") (pinfunction "PB6_58") (pintype "bidirectional"))
    )
    (net (code "87") (name "unconnected-(U$1-PB7-Pad59)") (class "Default")
      (node (ref "U$1") (pin "59") (pinfunction "PB7_59") (pintype "bidirectional"))
    )
    (net (code "88") (name "unconnected-(U$1-PB10-Pad29)") (class "Default")
      (node (ref "U$1") (pin "29") (pinfunction "PB10_29") (pintype "bidirectional"))
    )
    (net (code "89") (name "unconnected-(U$1-PB14{slash}I2S2_XD-Pad35)") (class "Default")
      (node (ref "U$1") (pin "35") (pinfunction "PB14/I2S2_XD_35") (pintype "bidirectional"))
    )
    (net (code "90") (name "unconnected-(U$1-PC0-Pad8)") (class "Default")
      (node (ref "U$1") (pin "8") (pinfunction "PC0_8") (pintype "bidirectional"))
    )
    (net (code "91") (name "unconnected-(U$1-PC1-Pad9)") (class "Default")
      (node (ref "U$1") (pin "9") (pinfunction "PC1_9") (pintype "bidirectional"))
    )
    (net (code "92") (name "unconnected-(U$1-PC2-Pad10)") (class "Default")
      (node (ref "U$1") (pin "10") (pinfunction "PC2_10") (pintype "bidirectional"))
    )
    (net (code "93") (name "unconnected-(U$1-PC3-Pad11)") (class "Default")
      (node (ref "U$1") (pin "11") (pinfunction "PC3_11") (pintype "bidirectional"))
    )
    (net (code "94") (name "unconnected-(U$1-PC4-Pad24)") (class "Default")
      (node (ref "U$1") (pin "24") (pinfunction "PC4_24") (pintype "bidirectional"))
    )
    (net (code "95") (name "unconnected-(U$1-PC6{slash}I2S2_MCK-Pad37)") (class "Default")
      (node (ref "U$1") (pin "37") (pinfunction "PC6/I2S2_MCK_37") (pintype "bidirectional"))
    )
    (net (code "96") (name "unconnected-(U$1-PC7-Pad38)") (class "Default")
      (node (ref "U$1") (pin "38") (pinfunction "PC7_38") (pintype "bidirectional"))
    )
    (net (code "97") (name "unconnected-(U$1-PC8{slash}SDIO_D0-Pad39)") (class "Default")
      (node (ref "U$1") (pin "39") (pinfunction "PC8/SDIO_D0_39") (pintype "bidirectional"))
    )
    (net (code "98") (name "unconnected-(U$1-PC9{slash}SDIO_D1-Pad40)") (class "Default")
      (node (ref "U$1") (pin "40") (pinfunction "PC9/SDIO_D1_40") (pintype "bidirectional"))
    )
    (net (code "99") (name "unconnected-(U$1-PC10{slash}SDIO_D2-Pad51)") (class "Default")
      (node (ref "U$1") (pin "51") (pinfunction "PC10/SDIO_D2_51") (pintype "bidirectional"))
    )
    (net (code "100") (name "unconnected-(U$1-PC11{slash}SDIO_D3-Pad52)") (class "Default")
      (node (ref "U$1") (pin "52") (pinfunction "PC11/SDIO_D3_52") (pintype "bidirectional"))
    )
    (net (code "101") (name "unconnected-(U$1-PC12{slash}SDIO_CLK-Pad53)") (class "Default")
      (node (ref "U$1") (pin "53") (pinfunction "PC12/SDIO_CLK_53") (pintype "bidirectional"))
    )
    (net (code "102") (name "unconnected-(U$1-PC13-Pad2)") (class "Default")
      (node (ref "U$1") (pin "2") (pinfunction "PC13_2") (pintype "bidirectional"))
    )
    (net (code "103") (name "unconnected-(U$1-PC14-Pad3)") (class "Default")
      (node (ref "U$1") (pin "3") (pinfunction "PC14_3") (pintype "bidirectional"))
    )
    (net (code "104") (name "unconnected-(U$1-PC15-Pad4)") (class "Default")
      (node (ref "U$1") (pin "4") (pinfunction "PC15_4") (pintype "bidirectional"))
    )
    (net (code "105") (name "unconnected-(U$1-PD2{slash}SDIO_CMD-Pad54)") (class "Default")
      (node (ref "U$1") (pin "54") (pinfunction "PD2/SDIO_CMD_54") (pintype "bidirectional"))
    )
    (net (code "106") (name "unconnected-(U$3-PA0-Pad14)") (class "Default")
      (node (ref "U$3") (pin "14") (pinfunction "PA0_14") (pintype "bidirectional"))
    )
    (net (code "107") (name "unconnected-(U$3-PA1-Pad15)") (class "Default")
      (node (ref "U$3") (pin "15") (pinfunction "PA1_15") (pintype "bidirectional"))
    )
    (net (code "108") (name "unconnected-(U$3-PA8-Pad41)") (class "Default")
      (node (ref "U$3") (pin "41") (pinfunction "PA8_41") (pintype "bidirectional"))
    )
    (net (code "109") (name "unconnected-(U$3-PA9{slash}UART1_TX-Pad42)") (class "Default")
      (node (ref "U$3") (pin "42") (pinfunction "PA9/UART1_TX_42") (pintype "bidirectional"))
    )
    (net (code "110") (name "unconnected-(U$3-PA10{slash}UART1_RX-Pad43)") (class "Default")
      (node (ref "U$3") (pin "43") (pinfunction "PA10/UART1_RX_43") (pintype "bidirectional"))
    )
    (net (code "111") (name "unconnected-(U$3-PA11-Pad44)") (class "Default")
      (node (ref "U$3") (pin "44") (pinfunction "PA11_44") (pintype "bidirectional"))
    )
    (net (code "112") (name "unconnected-(U$3-PA12-Pad45)") (class "Default")
      (node (ref "U$3") (pin "45") (pinfunction "PA12_45") (pintype "bidirectional"))
    )
    (net (code "113") (name "unconnected-(U$3-PA15{slash}JTDI-Pad50)") (class "Default")
      (node (ref "U$3") (pin "50") (pinfunction "PA15/JTDI_50") (pintype "bidirectional"))
    )
    (net (code "114") (name "unconnected-(U$3-PB0-Pad26)") (class "Default")
      (node (ref "U$3") (pin "26") (pinfunction "PB0_26") (pintype "bidirectional"))
    )
    (net (code "115") (name "unconnected-(U$3-PB1-Pad27)") (class "Default")
      (node (ref "U$3") (pin "27") (pinfunction "PB1_27") (pintype "bidirectional"))
    )
    (net (code "116") (name "unconnected-(U$3-PB2-BOOT1-Pad28)") (class "Default")
      (node (ref "U$3") (pin "28") (pinfunction "PB2-BOOT1_28") (pintype "bidirectional"))
    )
    (net (code "117") (name "unconnected-(U$3-PB4{slash}JTRST-Pad56)") (class "Default")
      (node (ref "U$3") (pin "56") (pinfunction "PB4/JTRST_56") (pintype "bidirectional"))
    )
    (net (code "118") (name "unconnected-(U$3-PB5-Pad57)") (class "Default")
      (node (ref "U$3") (pin "57") (pinfunction "PB5_57") (pintype "bidirectional"))
    )
    (net (code "119") (name "unconnected-(U$3-PB6-Pad58)") (class "Default")
      (node (ref "U$3") (pin "58") (pinfunction "PB6_58") (pintype "bidirectional"))
    )
    (net (code "120") (name "unconnected-(U$3-PB7-Pad59)") (class "Default")
      (node (ref "U$3") (pin "59") (pinfunction "PB7_59") (pintype "bidirectional"))
    )
    (net (code "121") (name "unconnected-(U$3-PB10-Pad29)") (class "Default")
      (node (ref "U$3") (pin "29") (pinfunction "PB10_29") (pintype "bidirectional"))
    )
    (net (code "122") (name "unconnected-(U$3-PB14{slash}I2S2_XD-Pad35)") (class "Default")
      (node (ref "U$3") (pin "35") (pinfunction "PB14/I2S2_XD_35") (pintype "bidirectional"))
    )
    (net (code "123") (name "unconnected-(U$3-PC0-Pad8)") (class "Default")
      (node (ref "U$3") (pin "8") (pinfunction "PC0_8") (pintype "bidirectional"))
    )
    (net (code "124") (name "unconnected-(U$3-PC1-Pad9)") (class "Default")
      (node (ref "U$3") (pin "9") (pinfunction "PC1_9") (pintype "bidirectional"))
    )
    (net (code "125") (name "unconnected-(U$3-PC2-Pad10)") (class "Default")
      (node (ref "U$3") (pin "10") (pinfunction "PC2_10") (pintype "bidirectional"))
    )
    (net (code "126") (name "unconnected-(U$3-PC3-Pad11)") (class "Default")
      (node (ref "U$3") (pin "11") (pinfunction "PC3_11") (pintype "bidirectional"))
    )
    (net (code "127") (name "unconnected-(U$3-PC4-Pad24)") (class "Default")
      (node (ref "U$3") (pin "24") (pinfunction "PC4_24") (pintype "bidirectional"))
    )
    (net (code "128") (name "unconnected-(U$3-PC6{slash}I2S2_MCK-Pad37)") (class "Default")
      (node (ref "U$3") (pin "37") (pinfunction "PC6/I2S2_MCK_37") (pintype "bidirectional"))
    )
    (net (code "129") (name "unconnected-(U$3-PC7-Pad38)") (class "Default")
      (node (ref "U$3") (pin "38") (pinfunction "PC7_38") (pintype "bidirectional"))
    )
    (net (code "130") (name "unconnected-(U$3-PC8{slash}SDIO_D0-Pad39)") (class "Default")
      (node (ref "U$3") (pin "39") (pinfunction "PC8/SDIO_D0_39") (pintype "bidirectional"))
    )
    (net (code "131") (name "unconnected-(U$3-PC9{slash}SDIO_D1-Pad40)") (class "Default")
      (node (ref "U$3") (pin "40") (pinfunction "PC9/SDIO_D1_40") (pintype "bidirectional"))
    )
    (net (code "132") (name "unconnected-(U$3-PC10{slash}SDIO_D2-Pad51)") (class "Default")
      (node (ref "U$3") (pin "51") (pinfunction "PC10/SDIO_D2_51") (pintype "bidirectional"))
    )
    (net (code "133") (name "unconnected-(U$3-PC11{slash}SDIO_D3-Pad52)") (class "Default")
      (node (ref "U$3") (pin "52") (pinfunction "PC11/SDIO_D3_52") (pintype "bidirectional"))
    )
    (net (code "134") (name "unconnected-(U$3-PC12{slash}SDIO_CLK-Pad53)") (class "Default")
      (node (ref "U$3") (pin "53") (pinfunction "PC12/SDIO_CLK_53") (pintype "bidirectional"))
    )
    (net (code "135") (name "unconnected-(U$3-PC13-Pad2)") (class "Default")
      (node (ref "U$3") (pin "2") (pinfunction "PC13_2") (pintype "bidirectional"))
    )
    (net (code "136") (name "unconnected-(U$3-PC14-Pad3)") (class "Default")
      (node (ref "U$3") (pin "3") (pinfunction "PC14_3") (pintype "bidirectional"))
    )
    (net (code "137") (name "unconnected-(U$3-PC15-Pad4)") (class "Default")
      (node (ref "U$3") (pin "4") (pinfunction "PC15_4") (pintype "bidirectional"))
    )
    (net (code "138") (name "unconnected-(U$3-PD2{slash}SDIO_CMD-Pad54)") (class "Default")
      (node (ref "U$3") (pin "54") (pinfunction "PD2/SDIO_CMD_54") (pintype "bidirectional"))
    )
  )
)
